# 0HP_EYEtenuator_REV_1.net
KiCad netlist of a schematic drawn in EAGLE
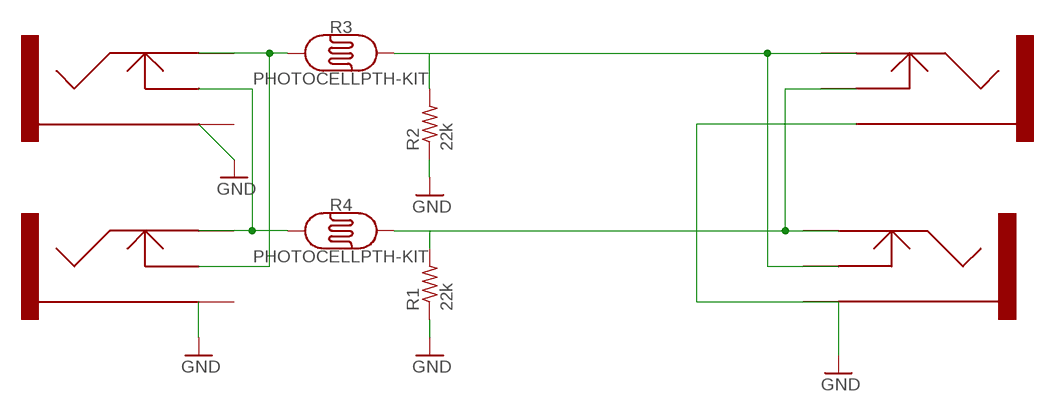
[diagram p0: schematic, sheet 1]

(export (version "E")
  (design (tool "Eeschema 10.0.6"))
  (components
    (comp (ref "CV1")
      (value "3.5MMJACK")
      (footprint "eagle-import:3.5MMPHONEJACK")
      (libsource (lib "eagle-import") (part "3.5MMJACK"))
    )
    (comp (ref "CV2")
      (value "3.5MMJACK")
      (footprint "eagle-import:3.5MMPHONEJACK")
      (libsource (lib "eagle-import") (part "3.5MMJACK"))
    )
    (comp (ref "IN")
      (value "3.5MMJACK")
      (footprint "eagle-import:3.5MMPHONEJACK")
      (libsource (lib "eagle-import") (part "3.5MMJACK"))
    )
    (comp (ref "OUT")
      (value "3.5MMJACK")
      (footprint "eagle-import:3.5MMPHONEJACK")
      (libsource (lib "eagle-import") (part "3.5MMJACK"))
    )
    (comp (ref "R1")
      (value "22k")
      (footprint "eagle-import:0207_2V")
      (libsource (lib "eagle-import") (part "R-US_0207/2V"))
    )
    (comp (ref "R2")
      (value "22k")
      (footprint "eagle-import:0207_2V")
      (libsource (lib "eagle-import") (part "R-US_0207/2V"))
    )
    (comp (ref "R3")
      (value "PHOTOCELLPTH-KIT")
      (footprint "eagle-import:PHOTOCELL-KIT")
      (libsource (lib "eagle-import") (part "PHOTOCELLPTH-KIT"))
    )
    (comp (ref "R4")
      (value "PHOTOCELLPTH-KIT")
      (footprint "eagle-import:PHOTOCELL-KIT")
      (libsource (lib "eagle-import") (part "PHOTOCELLPTH-KIT"))
    )
  )
  (nets
    (net (code "1") (name "GND") (class "Default")
      (node (ref "CV1") (pin "SLEEVE") (pinfunction "SLEEVE_SLEEVE") (pintype "bidirectional"))
      (node (ref "CV2") (pin "SLEEVE") (pinfunction "SLEEVE_SLEEVE") (pintype "bidirectional"))
      (node (ref "IN") (pin "SLEEVE") (pinfunction "SLEEVE_SLEEVE") (pintype "bidirectional"))
      (node (ref "OUT") (pin "SLEEVE") (pinfunction "SLEEVE_SLEEVE") (pintype "bidirectional"))
      (node (ref "R1") (pin "1") (pinfunction "1_1") (pintype "passive"))
      (node (ref "R2") (pin "1") (pinfunction "1_1") (pintype "passive"))
    )
    (net (code "2") (name "Net-(R3-P$1)") (class "Default")
      (node (ref "CV1") (pin "SWITCH") (pinfunction "SWITCH_SWITCH") (pintype "bidirectional"))
      (node (ref "CV2") (pin "TIP") (pinfunction "TIP_TIP") (pintype "bidirectional"))
      (node (ref "R3") (pin "1") (pinfunction "P$1_1") (pintype "bidirectional"))
    )
    (net (code "3") (name "Net-(R3-P$2)") (class "Default")
      (node (ref "IN") (pin "SWITCH") (pinfunction "SWITCH_SWITCH") (pintype "bidirectional"))
      (node (ref "OUT") (pin "TIP") (pinfunction "TIP_TIP") (pintype "bidirectional"))
      (node (ref "R2") (pin "2") (pinfunction "2_2") (pintype "passive"))
      (node (ref "R3") (pin "2") (pinfunction "P$2_2") (pintype "bidirectional"))
    )
    (net (code "4") (name "Net-(R4-P$1)") (class "Default")
      (node (ref "CV1") (pin "TIP") (pinfunction "TIP_TIP") (pintype "bidirectional"))
      (node (ref "CV2") (pin "SWITCH") (pinfunction "SWITCH_SWITCH") (pintype "bidirectional"))
      (node (ref "R4") (pin "1") (pinfunction "P$1_1") (pintype "bidirectional"))
    )
    (net (code "5") (name "Net-(R4-P$2)") (class "Default")
      (node (ref "IN") (pin "TIP") (pinfunction "TIP_TIP") (pintype "bidirectional"))
      (node (ref "OUT") (pin "SWITCH") (pinfunction "SWITCH_SWITCH") (pintype "bidirectional"))
      (node (ref "R1") (pin "2") (pinfunction "2_2") (pintype "passive"))
      (node (ref "R4") (pin "2") (pinfunction "P$2_2") (pintype "bidirectional"))
    )
  )
)
